# stylophone.net
KiCad netlist of a schematic drawn in EAGLE
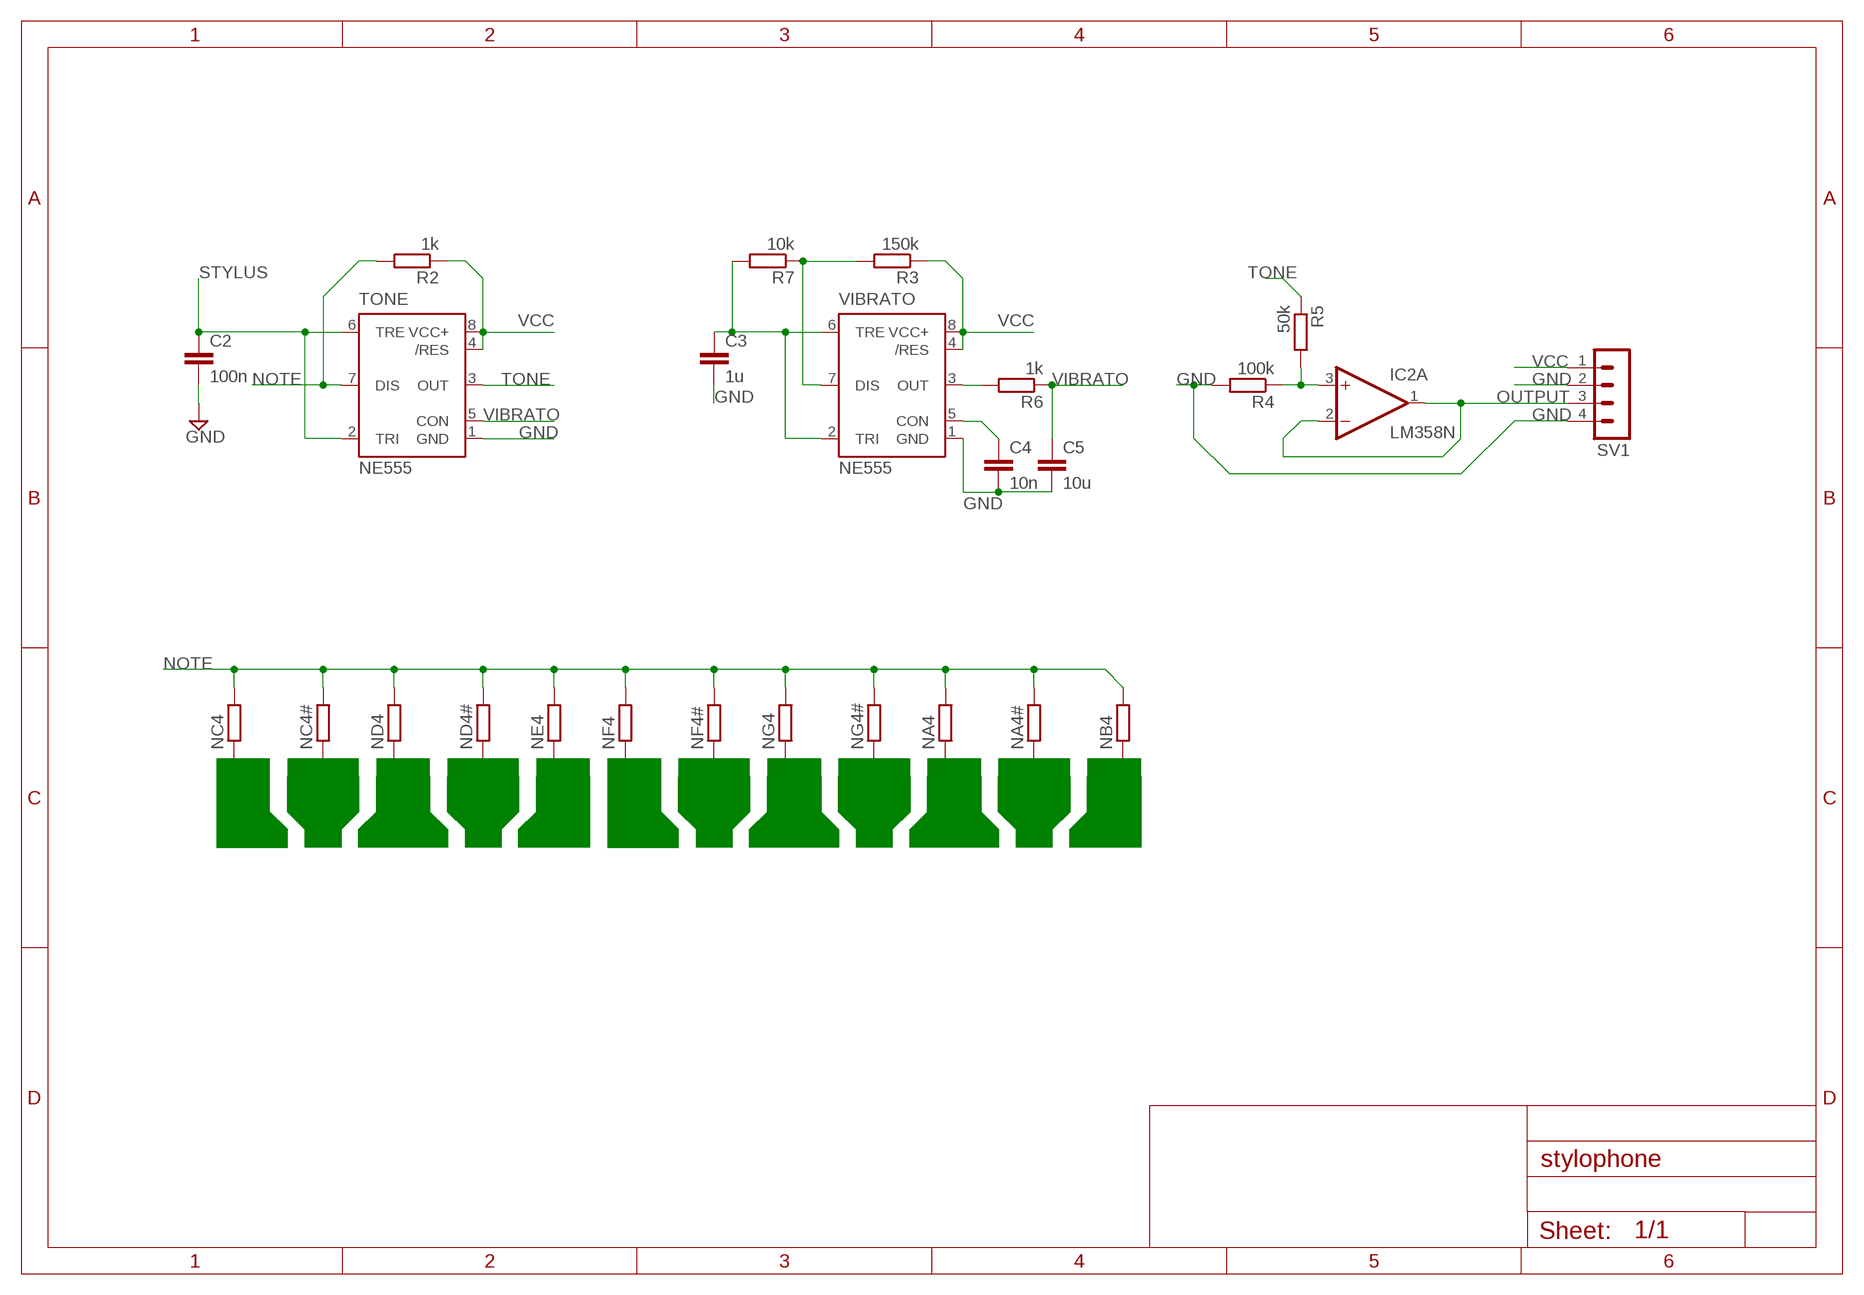
[diagram p0: schematic, sheet 1]

(export (version "E")
  (design (tool "Eeschema 10.0.6"))
  (components
    (comp (ref "C2")
      (value "100n")
      (footprint "eagle-import:C2.5-5")
      (libsource (lib "eagle-import") (part "C2.5/5"))
    )
    (comp (ref "C3")
      (value "1u")
      (footprint "eagle-import:C2.5-5")
      (libsource (lib "eagle-import") (part "C2.5/5"))
    )
    (comp (ref "C4")
      (value "10n")
      (footprint "eagle-import:C2.5-5")
      (libsource (lib "eagle-import") (part "C2.5/5"))
    )
    (comp (ref "C5")
      (value "10u")
      (footprint "eagle-import:C2.5-5")
      (libsource (lib "eagle-import") (part "C2.5/5"))
    )
    (comp (ref "IC2")
      (value "LM358N")
      (footprint "eagle-import:DIL08")
      (libsource (lib "eagle-import") (part "LM358N"))
    )
    (comp (ref "NA4")
      (value "R-EU_M1206")
      (footprint "eagle-import:M1206")
      (libsource (lib "eagle-import") (part "R-EU_M1206"))
    )
    (comp (ref "NA4#")
      (value "R-EU_M1206")
      (footprint "eagle-import:M1206")
      (libsource (lib "eagle-import") (part "R-EU_M1206"))
    )
    (comp (ref "NB4")
      (value "R-EU_M1206")
      (footprint "eagle-import:M1206")
      (libsource (lib "eagle-import") (part "R-EU_M1206"))
    )
    (comp (ref "NC4")
      (value "R-EU_M1206")
      (footprint "eagle-import:M1206")
      (libsource (lib "eagle-import") (part "R-EU_M1206"))
    )
    (comp (ref "NC4#")
      (value "R-EU_M1206")
      (footprint "eagle-import:M1206")
      (libsource (lib "eagle-import") (part "R-EU_M1206"))
    )
    (comp (ref "ND4")
      (value "R-EU_M1206")
      (footprint "eagle-import:M1206")
      (libsource (lib "eagle-import") (part "R-EU_M1206"))
    )
    (comp (ref "ND4#")
      (value "R-EU_M1206")
      (footprint "eagle-import:M1206")
      (libsource (lib "eagle-import") (part "R-EU_M1206"))
    )
    (comp (ref "NE4")
      (value "R-EU_M1206")
      (footprint "eagle-import:M1206")
      (libsource (lib "eagle-import") (part "R-EU_M1206"))
    )
    (comp (ref "NF4")
      (value "R-EU_M1206")
      (footprint "eagle-import:M1206")
      (libsource (lib "eagle-import") (part "R-EU_M1206"))
    )
    (comp (ref "NF4#")
      (value "R-EU_M1206")
      (footprint "eagle-import:M1206")
      (libsource (lib "eagle-import") (part "R-EU_M1206"))
    )
    (comp (ref "NG4")
      (value "R-EU_M1206")
      (footprint "eagle-import:M1206")
      (libsource (lib "eagle-import") (part "R-EU_M1206"))
    )
    (comp (ref "NG4#")
      (value "R-EU_M1206")
      (footprint "eagle-import:M1206")
      (libsource (lib "eagle-import") (part "R-EU_M1206"))
    )
    (comp (ref "R2")
      (value "1k")
      (footprint "eagle-import:M1206")
      (libsource (lib "eagle-import") (part "R-EU_M1206"))
    )
    (comp (ref "R3")
      (value "150k")
      (footprint "eagle-import:M1206")
      (libsource (lib "eagle-import") (part "R-EU_M1206"))
    )
    (comp (ref "R4")
      (value "100k")
      (footprint "eagle-import:M1206")
      (libsource (lib "eagle-import") (part "R-EU_M1206"))
    )
    (comp (ref "R5")
      (value "50k")
      (footprint "eagle-import:M1206")
      (libsource (lib "eagle-import") (part "R-EU_M1206"))
    )
    (comp (ref "R6")
      (value "1k")
      (footprint "eagle-import:M1206")
      (libsource (lib "eagle-import") (part "R-EU_M1206"))
    )
    (comp (ref "R7")
      (value "10k")
      (footprint "eagle-import:0204_7")
      (libsource (lib "eagle-import") (part "R-EU_0204/7"))
    )
    (comp (ref "SV1")
      (value "MA04-1")
      (footprint "eagle-import:MA04-1")
      (libsource (lib "eagle-import") (part "MA04-1"))
    )
    (comp (ref "TONE")
      (value "NE555")
      (footprint "eagle-import:DIL-08")
      (fields (field (name "MF") "Arrow Electronics") (field (name "MPN") "NE555N"))
      (libsource (lib "eagle-import") (part "NE555"))
    )
    (comp (ref "VIBRATO")
      (value "NE555")
      (footprint "eagle-import:DIL-08")
      (fields (field (name "MF") "Arrow Electronics") (field (name "MPN") "NE555N"))
      (libsource (lib "eagle-import") (part "NE555"))
    )
  )
  (nets
    (net (code "1") (name "/NOTE") (class "Default")
      (node (ref "NA4") (pin "2") (pinfunction "2_2") (pintype "passive"))
      (node (ref "NA4#") (pin "2") (pinfunction "2_2") (pintype "passive"))
      (node (ref "NB4") (pin "2") (pinfunction "2_2") (pintype "passive"))
      (node (ref "NC4") (pin "2") (pinfunction "2_2") (pintype "passive"))
      (node (ref "NC4#") (pin "2") (pinfunction "2_2") (pintype "passive"))
      (node (ref "ND4") (pin "2") (pinfunction "2_2") (pintype "passive"))
      (node (ref "ND4#") (pin "2") (pinfunction "2_2") (pintype "passive"))
      (node (ref "NE4") (pin "2") (pinfunction "2_2") (pintype "passive"))
      (node (ref "NF4") (pin "2") (pinfunction "2_2") (pintype "passive"))
      (node (ref "NF4#") (pin "2") (pinfunction "2_2") (pintype "passive"))
      (node (ref "NG4") (pin "2") (pinfunction "2_2") (pintype "passive"))
      (node (ref "NG4#") (pin "2") (pinfunction "2_2") (pintype "passive"))
      (node (ref "R2") (pin "2") (pinfunction "2_2") (pintype "passive"))
      (node (ref "TONE") (pin "7") (pinfunction "DIS_7") (pintype "input"))
    )
    (net (code "2") (name "/OUTPUT") (class "Default")
      (node (ref "IC2") (pin "1") (pinfunction "OUT_1") (pintype "output"))
      (node (ref "IC2") (pin "2") (pinfunction "-IN_2") (pintype "input"))
      (node (ref "SV1") (pin "3") (pinfunction "3_3") (pintype "passive"))
    )
    (net (code "3") (name "/STYLUS") (class "Default")
      (node (ref "C2") (pin "1") (pinfunction "1_1") (pintype "passive"))
      (node (ref "TONE") (pin "2") (pinfunction "TRI_2") (pintype "input"))
      (node (ref "TONE") (pin "6") (pinfunction "TRE_6") (pintype "input"))
    )
    (net (code "4") (name "/TONE") (class "Default")
      (node (ref "R5") (pin "1") (pinfunction "1_1") (pintype "passive"))
      (node (ref "TONE") (pin "3") (pinfunction "OUT_3") (pintype "output"))
    )
    (net (code "5") (name "/VCC") (class "Default")
      (node (ref "R2") (pin "1") (pinfunction "1_1") (pintype "passive"))
      (node (ref "R3") (pin "1") (pinfunction "1_1") (pintype "passive"))
      (node (ref "SV1") (pin "1") (pinfunction "1_1") (pintype "passive"))
      (node (ref "TONE") (pin "4") (pinfunction "/RES_4") (pintype "input"))
      (node (ref "TONE") (pin "8") (pinfunction "VCC+_8") (pintype "power_in"))
      (node (ref "VIBRATO") (pin "4") (pinfunction "/RES_4") (pintype "input"))
      (node (ref "VIBRATO") (pin "8") (pinfunction "VCC+_8") (pintype "power_in"))
    )
    (net (code "6") (name "/VIBRATO") (class "Default")
      (node (ref "C5") (pin "1") (pinfunction "1_1") (pintype "passive"))
      (node (ref "R6") (pin "1") (pinfunction "1_1") (pintype "passive"))
      (node (ref "TONE") (pin "5") (pinfunction "CON_5") (pintype "input"))
    )
    (net (code "7") (name "GND") (class "Default")
      (node (ref "C2") (pin "2") (pinfunction "2_2") (pintype "passive"))
      (node (ref "C3") (pin "2") (pinfunction "2_2") (pintype "passive"))
      (node (ref "C4") (pin "2") (pinfunction "2_2") (pintype "passive"))
      (node (ref "C5") (pin "2") (pinfunction "2_2") (pintype "passive"))
      (node (ref "R4") (pin "2") (pinfunction "2_2") (pintype "passive"))
      (node (ref "SV1") (pin "2") (pinfunction "2_2") (pintype "passive"))
      (node (ref "SV1") (pin "4") (pinfunction "4_4") (pintype "passive"))
      (node (ref "TONE") (pin "1") (pinfunction "GND_1") (pintype "power_in"))
      (node (ref "VIBRATO") (pin "1") (pinfunction "GND_1") (pintype "power_in"))
    )
    (net (code "8") (name "Net-(IC2A-+IN)") (class "Default")
      (node (ref "IC2") (pin "3") (pinfunction "+IN_3") (pintype "input"))
      (node (ref "R4") (pin "1") (pinfunction "1_1") (pintype "passive"))
      (node (ref "R5") (pin "2") (pinfunction "2_2") (pintype "passive"))
    )
    (net (code "9") (name "Net-(VIBRATO-CON)") (class "Default")
      (node (ref "C4") (pin "1") (pinfunction "1_1") (pintype "passive"))
      (node (ref "VIBRATO") (pin "5") (pinfunction "CON_5") (pintype "input"))
    )
    (net (code "10") (name "Net-(VIBRATO-DIS)") (class "Default")
      (node (ref "R3") (pin "2") (pinfunction "2_2") (pintype "passive"))
      (node (ref "R7") (pin "1") (pinfunction "1_1") (pintype "passive"))
      (node (ref "VIBRATO") (pin "7") (pinfunction "DIS_7") (pintype "input"))
    )
    (net (code "11") (name "Net-(VIBRATO-OUT)") (class "Default")
      (node (ref "R6") (pin "2") (pinfunction "2_2") (pintype "passive"))
      (node (ref "VIBRATO") (pin "3") (pinfunction "OUT_3") (pintype "output"))
    )
    (net (code "12") (name "Net-(VIBRATO-TRE)") (class "Default")
      (node (ref "C3") (pin "1") (pinfunction "1_1") (pintype "passive"))
      (node (ref "R7") (pin "2") (pinfunction "2_2") (pintype "passive"))
      (node (ref "VIBRATO") (pin "2") (pinfunction "TRI_2") (pintype "input"))
      (node (ref "VIBRATO") (pin "6") (pinfunction "TRE_6") (pintype "input"))
    )
    (net (code "13") (name "unconnected-(NA4#-Pad1)") (class "Default")
      (node (ref "NA4#") (pin "1") (pinfunction "1_1") (pintype "passive"))
    )
    (net (code "14") (name "unconnected-(NA4-Pad1)") (class "Default")
      (node (ref "NA4") (pin "1") (pinfunction "1_1") (pintype "passive"))
    )
    (net (code "15") (name "unconnected-(NB4-Pad1)") (class "Default")
      (node (ref "NB4") (pin "1") (pinfunction "1_1") (pintype "passive"))
    )
    (net (code "16") (name "unconnected-(NC4#-Pad1)") (class "Default")
      (node (ref "NC4#") (pin "1") (pinfunction "1_1") (pintype "passive"))
    )
    (net (code "17") (name "unconnected-(NC4-Pad1)") (class "Default")
      (node (ref "NC4") (pin "1") (pinfunction "1_1") (pintype "passive"))
    )
    (net (code "18") (name "unconnected-(ND4#-Pad1)") (class "Default")
      (node (ref "ND4#") (pin "1") (pinfunction "1_1") (pintype "passive"))
    )
    (net (code "19") (name "unconnected-(ND4-Pad1)") (class "Default")
      (node (ref "ND4") (pin "1") (pinfunction "1_1") (pintype "passive"))
    )
    (net (code "20") (name "unconnected-(NE4-Pad1)") (class "Default")
      (node (ref "NE4") (pin "1") (pinfunction "1_1") (pintype "passive"))
    )
    (net (code "21") (name "unconnected-(NF4#-Pad1)") (class "Default")
      (node (ref "NF4#") (pin "1") (pinfunction "1_1") (pintype "passive"))
    )
    (net (code "22") (name "unconnected-(NF4-Pad1)") (class "Default")
      (node (ref "NF4") (pin "1") (pinfunction "1_1") (pintype "passive"))
    )
    (net (code "23") (name "unconnected-(NG4#-Pad1)") (class "Default")
      (node (ref "NG4#") (pin "1") (pinfunction "1_1") (pintype "passive"))
    )
    (net (code "24") (name "unconnected-(NG4-Pad1)") (class "Default")
      (node (ref "NG4") (pin "1") (pinfunction "1_1") (pintype "passive"))
    )
  )
)
